# BC817_OC.net
KiCad netlist of a schematic drawn in Altium Designer
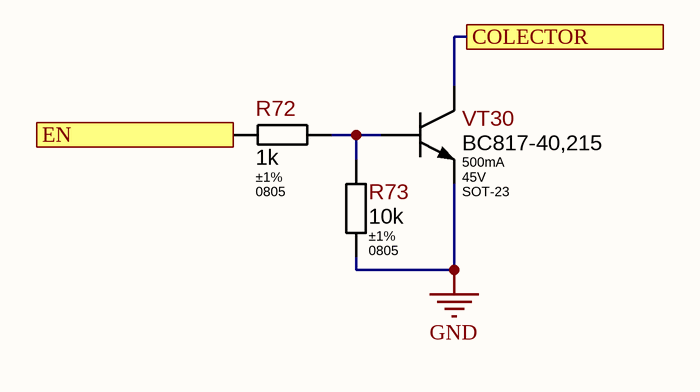
[diagram p0: BC817_OC.SchDoc]

(export (version "E")
  (design (tool "Eeschema 10.0.6"))
  (components
    (comp (ref "R72")
      (value "1k")
      (footprint "R_ANY_CHIP_0805_MED")
      (description "1 kOhms ±1%, 1/8W 0805 Thick Film Resistor")
      (fields
        (field (name "TOLERANCE") "±1%")
        (field (name "PACKAGE") "0805")
        (field (name "PART NUMBER") "RC0805FR-0710K2L")
        (field (name "MANUFACTURER") "Yageo")
      )
      (libsource (lib "resistors") (part "RC0805FR-0710K2L"))
    )
    (comp (ref "R73")
      (value "10k")
      (footprint "R_ANY_CHIP_0805_MED")
      (description "10 kOhms ±1%, 1/8W 0805 Thick Film Resistor")
      (fields
        (field (name "TOLERANCE") "±1%")
        (field (name "PACKAGE") "0805")
        (field (name "PART NUMBER") "RC0805FR-0710K2L")
        (field (name "MANUFACTURER") "Yageo")
      )
      (libsource (lib "resistors") (part "RC0805FR-0710K2L"))
    )
    (comp (ref "VT30")
      (value "BC817-40,215")
      (footprint "SOT-23_MED")
      (description "45V, 500mA NPN General Purpose Transistor")
      (fields
        (field (name "PART NUMBER") "BC817-40,215")
        (field (name "IC") "500mA")
        (field (name "VCE") "45V")
        (field (name "PACKAGE") "SOT-23")
        (field (name "MANUFACTURER") "Nexperia USA")
      )
      (libsource (lib "transistors") (part "BC817-40,215"))
    )
  )
  (nets
    (net (code "1") (name "/COLECTOR") (class "Default")
      (node (ref "VT30") (pin "3") (pinfunction "C_3") (pintype "passive"))
    )
    (net (code "2") (name "/EN") (class "Default") (node (ref "R72") (pin "1") (pintype "passive")))
    (net (code "3") (name "GND") (class "Default")
      (node (ref "R73") (pin "1") (pintype "passive"))
      (node (ref "VT30") (pin "2") (pinfunction "E_2") (pintype "passive"))
    )
    (net (code "4") (name "Net-(VT30-B)") (class "Default")
      (node (ref "R72") (pin "2") (pintype "passive"))
      (node (ref "R73") (pin "2") (pintype "passive"))
      (node (ref "VT30") (pin "1") (pinfunction "B_1") (pintype "passive"))
    )
  )
)
